# TeensySonarBoard.net
KiCad netlist of a schematic drawn in EAGLE
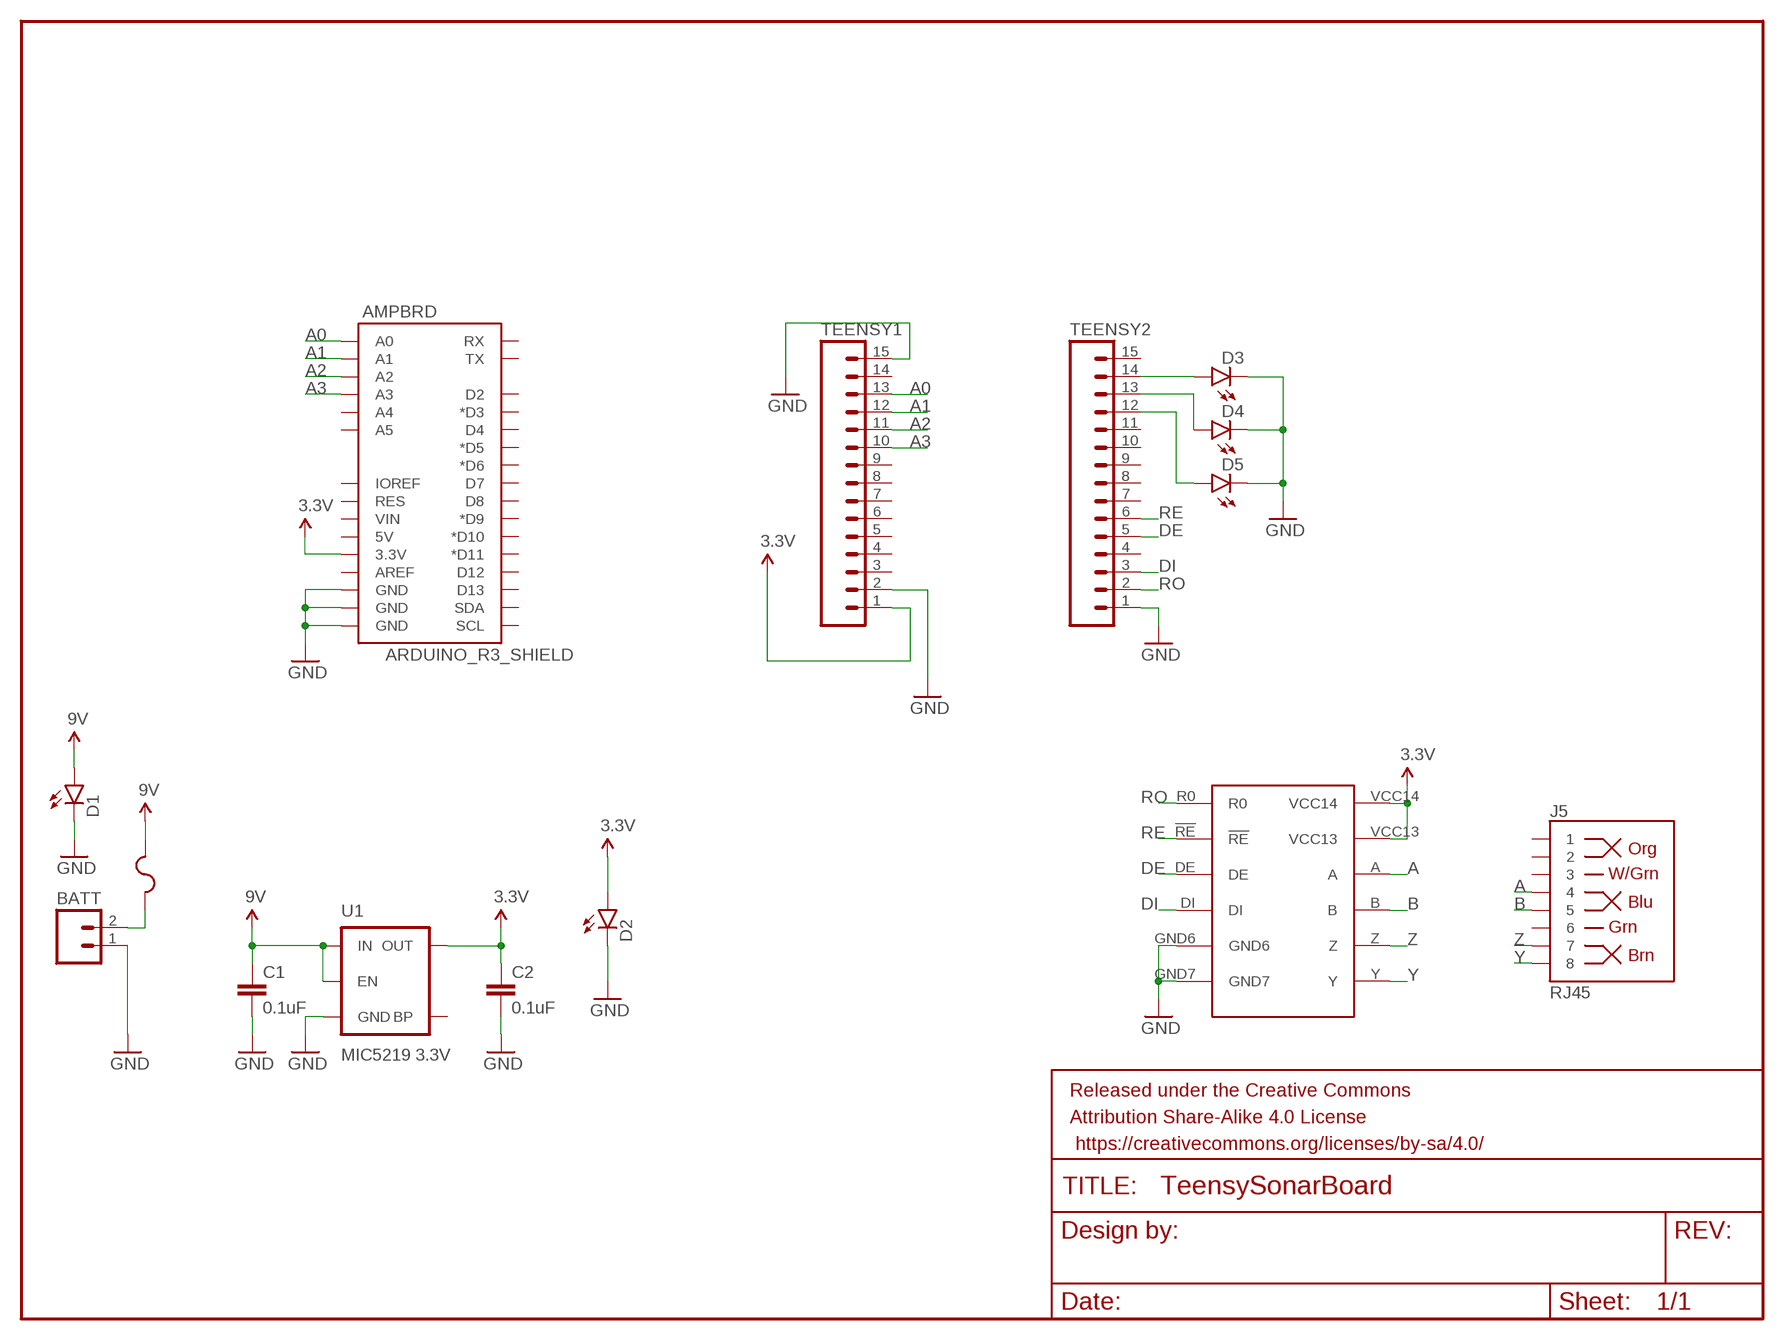
[diagram p0: schematic, sheet 1]

(export (version "E")
  (design (tool "Eeschema 10.0.6"))
  (components
    (comp (ref "AMPBRD")
      (value "ARDUINO_R3_SHIELD")
      (footprint "eagle-import:UNO_R3_SHIELD")
      (libsource (lib "eagle-import") (part "ARDUINO_R3_SHIELD"))
    )
    (comp (ref "BATT")
      (value "M02JST-PTH-VERT")
      (footprint "eagle-import:JST-2-PTH-VERT")
      (libsource (lib "eagle-import") (part "M02JST-PTH-VERT"))
    )
    (comp (ref "C1")
      (value "0.1uF")
      (footprint "eagle-import:0603-CAP")
      (libsource (lib "eagle-import") (part "CAP0603-CAP"))
    )
    (comp (ref "C2")
      (value "0.1uF")
      (footprint "eagle-import:0603-CAP")
      (libsource (lib "eagle-import") (part "CAP0603-CAP"))
    )
    (comp (ref "D1")
      (value "LED0603")
      (footprint "eagle-import:LED-0603")
      (libsource (lib "eagle-import") (part "LED0603"))
    )
    (comp (ref "D2")
      (value "LED0603")
      (footprint "eagle-import:LED-0603")
      (libsource (lib "eagle-import") (part "LED0603"))
    )
    (comp (ref "D3")
      (value "LED0603")
      (footprint "eagle-import:LED-0603")
      (libsource (lib "eagle-import") (part "LED0603"))
    )
    (comp (ref "D4")
      (value "LED0603")
      (footprint "eagle-import:LED-0603")
      (libsource (lib "eagle-import") (part "LED0603"))
    )
    (comp (ref "D5")
      (value "LED0603")
      (footprint "eagle-import:LED-0603")
      (libsource (lib "eagle-import") (part "LED0603"))
    )
    (comp (ref "F1")
      (value "2A")
      (footprint "eagle-import:KEYSTONE_FUSE_3587")
      (libsource (lib "eagle-import") (part "KEYSTONE_FUSE_3587"))
    )
    (comp (ref "FRAME1")
      (value "FRAME-LETTERNO_PACKAGE")
      (footprint "eagle-import:DUMMY")
      (fields (field (name "DESIGNER") "Nobody"))
      (libsource (lib "eagle-import") (part "FRAME-LETTERNO_PACKAGE"))
    )
    (comp (ref "J5")
      (value "RJ45")
      (footprint "eagle-import:RJ45-8")
      (libsource (lib "eagle-import") (part "RJ45-8PTH"))
    )
    (comp (ref "TEENSY1")
      (value "M15")
      (footprint "eagle-import:1X15")
      (libsource (lib "eagle-import") (part "M15"))
    )
    (comp (ref "TEENSY2")
      (value "M15")
      (footprint "eagle-import:1X15")
      (libsource (lib "eagle-import") (part "M15"))
    )
    (comp (ref "U$1")
      (value "MAX3491")
      (footprint "eagle-import:MAX3491")
      (libsource (lib "eagle-import") (part "MAX3491"))
    )
    (comp (ref "U1")
      (value "MIC5219 3.3V")
      (footprint "eagle-import:SOT23-5")
      (libsource (lib "eagle-import") (part "V_REG_MIC52193.3V"))
    )
  )
  (nets
    (net (code "1") (name "/A") (class "Default")
      (node (ref "J5") (pin "4") (pinfunction "4_4") (pintype "bidirectional"))
      (node (ref "U$1") (pin "A") (pinfunction "A_A") (pintype "bidirectional"))
    )
    (net (code "2") (name "/A0") (class "Default")
      (node (ref "AMPBRD") (pin "A0") (pinfunction "A0_A0") (pintype "bidirectional"))
      (node (ref "TEENSY1") (pin "13") (pinfunction "13_13") (pintype "passive"))
    )
    (net (code "3") (name "/A1") (class "Default")
      (node (ref "AMPBRD") (pin "A1") (pinfunction "A1_A1") (pintype "bidirectional"))
      (node (ref "TEENSY1") (pin "12") (pinfunction "12_12") (pintype "passive"))
    )
    (net (code "4") (name "/A2") (class "Default")
      (node (ref "AMPBRD") (pin "A2") (pinfunction "A2_A2") (pintype "bidirectional"))
      (node (ref "TEENSY1") (pin "11") (pinfunction "11_11") (pintype "passive"))
    )
    (net (code "5") (name "/A3") (class "Default")
      (node (ref "AMPBRD") (pin "A3") (pinfunction "A3_A3") (pintype "bidirectional"))
      (node (ref "TEENSY1") (pin "10") (pinfunction "10_10") (pintype "passive"))
    )
    (net (code "6") (name "/B") (class "Default")
      (node (ref "J5") (pin "5") (pinfunction "5_5") (pintype "bidirectional"))
      (node (ref "U$1") (pin "B") (pinfunction "B_B") (pintype "bidirectional"))
    )
    (net (code "7") (name "/DE") (class "Default")
      (node (ref "TEENSY2") (pin "5") (pinfunction "5_5") (pintype "passive"))
      (node (ref "U$1") (pin "DE") (pinfunction "DE_DE") (pintype "bidirectional"))
    )
    (net (code "8") (name "/DI") (class "Default")
      (node (ref "TEENSY2") (pin "3") (pinfunction "3_3") (pintype "passive"))
      (node (ref "U$1") (pin "DI") (pinfunction "DI_DI") (pintype "bidirectional"))
    )
    (net (code "9") (name "/RE") (class "Default")
      (node (ref "TEENSY2") (pin "6") (pinfunction "6_6") (pintype "passive"))
      (node (ref "U$1") (pin "!RE") (pinfunction "~{RE}_!RE") (pintype "bidirectional"))
    )
    (net (code "10") (name "/RO") (class "Default")
      (node (ref "TEENSY2") (pin "2") (pinfunction "2_2") (pintype "passive"))
      (node (ref "U$1") (pin "R0") (pinfunction "R0_R0") (pintype "bidirectional"))
    )
    (net (code "11") (name "/Y") (class "Default")
      (node (ref "J5") (pin "8") (pinfunction "8_8") (pintype "bidirectional"))
      (node (ref "U$1") (pin "Y") (pinfunction "Y_Y") (pintype "bidirectional"))
    )
    (net (code "12") (name "/Z") (class "Default")
      (node (ref "J5") (pin "7") (pinfunction "7_7") (pintype "bidirectional"))
      (node (ref "U$1") (pin "Z") (pinfunction "Z_Z") (pintype "bidirectional"))
    )
    (net (code "13") (name "3.3V") (class "Default")
      (node (ref "AMPBRD") (pin "3.3V") (pinfunction "3.3V_3.3V") (pintype "bidirectional"))
      (node (ref "C2") (pin "1") (pinfunction "1_1") (pintype "passive"))
      (node (ref "D2") (pin "A") (pinfunction "A_A") (pintype "passive"))
      (node (ref "TEENSY1") (pin "1") (pinfunction "1_1") (pintype "passive"))
      (node (ref "U$1") (pin "VCC13") (pinfunction "VCC13_VCC13") (pintype "bidirectional"))
      (node (ref "U$1") (pin "VCC14") (pinfunction "VCC14_VCC14") (pintype "bidirectional"))
      (node (ref "U1") (pin "5") (pinfunction "OUT_5") (pintype "passive"))
    )
    (net (code "14") (name "9V") (class "Default")
      (node (ref "C1") (pin "1") (pinfunction "1_1") (pintype "passive"))
      (node (ref "D1") (pin "A") (pinfunction "A_A") (pintype "passive"))
      (node (ref "F1") (pin "P$3") (pinfunction "P$2_P$3") (pintype "bidirectional"))
      (node (ref "F1") (pin "P$4") (pinfunction "P$2_P$4") (pintype "bidirectional"))
      (node (ref "U1") (pin "1") (pinfunction "IN_1") (pintype "input"))
      (node (ref "U1") (pin "3") (pinfunction "EN_3") (pintype "input"))
    )
    (net (code "15") (name "GND") (class "Default")
      (node (ref "AMPBRD") (pin "GND@0") (pinfunction "GND_GND@0") (pintype "bidirectional"))
      (node (ref "AMPBRD") (pin "GND@1") (pinfunction "GND_GND@1") (pintype "bidirectional"))
      (node (ref "AMPBRD") (pin "GND@2") (pinfunction "GND_GND@2") (pintype "bidirectional"))
      (node (ref "BATT") (pin "1") (pinfunction "1_1") (pintype "passive"))
      (node (ref "C1") (pin "2") (pinfunction "2_2") (pintype "passive"))
      (node (ref "C2") (pin "2") (pinfunction "2_2") (pintype "passive"))
      (node (ref "D1") (pin "C") (pinfunction "C_C") (pintype "passive"))
      (node (ref "D2") (pin "C") (pinfunction "C_C") (pintype "passive"))
      (node (ref "D3") (pin "C") (pinfunction "C_C") (pintype "passive"))
      (node (ref "D4") (pin "C") (pinfunction "C_C") (pintype "passive"))
      (node (ref "D5") (pin "C") (pinfunction "C_C") (pintype "passive"))
      (node (ref "TEENSY1") (pin "15") (pinfunction "15_15") (pintype "passive"))
      (node (ref "TEENSY1") (pin "2") (pinfunction "2_2") (pintype "passive"))
      (node (ref "TEENSY2") (pin "1") (pinfunction "1_1") (pintype "passive"))
      (node (ref "U$1") (pin "GND6") (pinfunction "GND6_GND6") (pintype "bidirectional"))
      (node (ref "U$1") (pin "GND7") (pinfunction "GND7_GND7") (pintype "bidirectional"))
      (node (ref "U1") (pin "2") (pinfunction "GND_2") (pintype "input"))
    )
    (net (code "16") (name "Net-(BATT-Pad2)") (class "Default")
      (node (ref "BATT") (pin "2") (pinfunction "2_2") (pintype "passive"))
      (node (ref "F1") (pin "P$1") (pinfunction "P$1_P$1") (pintype "bidirectional"))
      (node (ref "F1") (pin "P$2") (pinfunction "P$1_P$2") (pintype "bidirectional"))
    )
    (net (code "17") (name "Net-(D3-PadA)") (class "Default")
      (node (ref "D3") (pin "A") (pinfunction "A_A") (pintype "passive"))
      (node (ref "TEENSY2") (pin "14") (pinfunction "14_14") (pintype "passive"))
    )
    (net (code "18") (name "Net-(D4-PadA)") (class "Default")
      (node (ref "D4") (pin "A") (pinfunction "A_A") (pintype "passive"))
      (node (ref "TEENSY2") (pin "13") (pinfunction "13_13") (pintype "passive"))
    )
    (net (code "19") (name "Net-(D5-PadA)") (class "Default")
      (node (ref "D5") (pin "A") (pinfunction "A_A") (pintype "passive"))
      (node (ref "TEENSY2") (pin "12") (pinfunction "12_12") (pintype "passive"))
    )
    (net (code "20") (name "unconnected-(AMPBRD-*D3-PadD3)") (class "Default")
      (node (ref "AMPBRD") (pin "D3") (pinfunction "*D3_D3") (pintype "bidirectional"))
    )
    (net (code "21") (name "unconnected-(AMPBRD-*D5-PadD5)") (class "Default")
      (node (ref "AMPBRD") (pin "D5") (pinfunction "*D5_D5") (pintype "bidirectional"))
    )
    (net (code "22") (name "unconnected-(AMPBRD-*D6-PadD6)") (class "Default")
      (node (ref "AMPBRD") (pin "D6") (pinfunction "*D6_D6") (pintype "bidirectional"))
    )
    (net (code "23") (name "unconnected-(AMPBRD-*D9-PadD9)") (class "Default")
      (node (ref "AMPBRD") (pin "D9") (pinfunction "*D9_D9") (pintype "bidirectional"))
    )
    (net (code "24") (name "unconnected-(AMPBRD-*D10-PadD10)") (class "Default")
      (node (ref "AMPBRD") (pin "D10") (pinfunction "*D10_D10") (pintype "bidirectional"))
    )
    (net (code "25") (name "unconnected-(AMPBRD-*D11-PadD11)") (class "Default")
      (node (ref "AMPBRD") (pin "D11") (pinfunction "*D11_D11") (pintype "bidirectional"))
    )
    (net (code "26") (name "unconnected-(AMPBRD-Pad5V)") (class "Default")
      (node (ref "AMPBRD") (pin "5V") (pinfunction "5V_5V") (pintype "bidirectional"))
    )
    (net (code "27") (name "unconnected-(AMPBRD-PadA4)") (class "Default")
      (node (ref "AMPBRD") (pin "A4") (pinfunction "A4_A4") (pintype "bidirectional"))
    )
    (net (code "28") (name "unconnected-(AMPBRD-PadA5)") (class "Default")
      (node (ref "AMPBRD") (pin "A5") (pinfunction "A5_A5") (pintype "bidirectional"))
    )
    (net (code "29") (name "unconnected-(AMPBRD-PadAREF)") (class "Default")
      (node (ref "AMPBRD") (pin "AREF") (pinfunction "AREF_AREF") (pintype "bidirectional"))
    )
    (net (code "30") (name "unconnected-(AMPBRD-PadD2)") (class "Default")
      (node (ref "AMPBRD") (pin "D2") (pinfunction "D2_D2") (pintype "bidirectional"))
    )
    (net (code "31") (name "unconnected-(AMPBRD-PadD4)") (class "Default")
      (node (ref "AMPBRD") (pin "D4") (pinfunction "D4_D4") (pintype "bidirectional"))
    )
    (net (code "32") (name "unconnected-(AMPBRD-PadD7)") (class "Default")
      (node (ref "AMPBRD") (pin "D7") (pinfunction "D7_D7") (pintype "bidirectional"))
    )
    (net (code "33") (name "unconnected-(AMPBRD-PadD8)") (class "Default")
      (node (ref "AMPBRD") (pin "D8") (pinfunction "D8_D8") (pintype "bidirectional"))
    )
    (net (code "34") (name "unconnected-(AMPBRD-PadD12)") (class "Default")
      (node (ref "AMPBRD") (pin "D12") (pinfunction "D12_D12") (pintype "bidirectional"))
    )
    (net (code "35") (name "unconnected-(AMPBRD-PadD13)") (class "Default")
      (node (ref "AMPBRD") (pin "D13") (pinfunction "D13_D13") (pintype "bidirectional"))
    )
    (net (code "36") (name "unconnected-(AMPBRD-PadIOREF)") (class "Default")
      (node (ref "AMPBRD") (pin "IOREF") (pinfunction "IOREF_IOREF") (pintype "bidirectional"))
    )
    (net (code "37") (name "unconnected-(AMPBRD-PadRES)") (class "Default")
      (node (ref "AMPBRD") (pin "RES") (pinfunction "RES_RES") (pintype "bidirectional"))
    )
    (net (code "38") (name "unconnected-(AMPBRD-PadRX)") (class "Default")
      (node (ref "AMPBRD") (pin "RX") (pinfunction "RX_RX") (pintype "bidirectional"))
    )
    (net (code "39") (name "unconnected-(AMPBRD-PadSCL)") (class "Default")
      (node (ref "AMPBRD") (pin "SCL") (pinfunction "SCL_SCL") (pintype "bidirectional"))
    )
    (net (code "40") (name "unconnected-(AMPBRD-PadSDA)") (class "Default")
      (node (ref "AMPBRD") (pin "SDA") (pinfunction "SDA_SDA") (pintype "bidirectional"))
    )
    (net (code "41") (name "unconnected-(AMPBRD-PadTX)") (class "Default")
      (node (ref "AMPBRD") (pin "TX") (pinfunction "TX_TX") (pintype "bidirectional"))
    )
    (net (code "42") (name "unconnected-(AMPBRD-PadVIN)") (class "Default")
      (node (ref "AMPBRD") (pin "VIN") (pinfunction "VIN_VIN") (pintype "bidirectional"))
    )
    (net (code "43") (name "unconnected-(J5-Pad1)") (class "Default")
      (node (ref "J5") (pin "1") (pinfunction "1_1") (pintype "bidirectional"))
    )
    (net (code "44") (name "unconnected-(J5-Pad2)") (class "Default")
      (node (ref "J5") (pin "2") (pinfunction "2_2") (pintype "bidirectional"))
    )
    (net (code "45") (name "unconnected-(J5-Pad3)") (class "Default")
      (node (ref "J5") (pin "3") (pinfunction "3_3") (pintype "bidirectional"))
    )
    (net (code "46") (name "unconnected-(J5-Pad6)") (class "Default")
      (node (ref "J5") (pin "6") (pinfunction "6_6") (pintype "bidirectional"))
    )
    (net (code "47") (name "unconnected-(TEENSY1-Pad3)") (class "Default")
      (node (ref "TEENSY1") (pin "3") (pinfunction "3_3") (pintype "passive"))
    )
    (net (code "48") (name "unconnected-(TEENSY1-Pad4)") (class "Default")
      (node (ref "TEENSY1") (pin "4") (pinfunction "4_4") (pintype "passive"))
    )
    (net (code "49") (name "unconnected-(TEENSY1-Pad5)") (class "Default")
      (node (ref "TEENSY1") (pin "5") (pinfunction "5_5") (pintype "passive"))
    )
    (net (code "50") (name "unconnected-(TEENSY1-Pad6)") (class "Default")
      (node (ref "TEENSY1") (pin "6") (pinfunction "6_6") (pintype "passive"))
    )
    (net (code "51") (name "unconnected-(TEENSY1-Pad7)") (class "Default")
      (node (ref "TEENSY1") (pin "7") (pinfunction "7_7") (pintype "passive"))
    )
    (net (code "52") (name "unconnected-(TEENSY1-Pad8)") (class "Default")
      (node (ref "TEENSY1") (pin "8") (pinfunction "8_8") (pintype "passive"))
    )
    (net (code "53") (name "unconnected-(TEENSY1-Pad9)") (class "Default")
      (node (ref "TEENSY1") (pin "9") (pinfunction "9_9") (pintype "passive"))
    )
    (net (code "54") (name "unconnected-(TEENSY1-Pad14)") (class "Default")
      (node (ref "TEENSY1") (pin "14") (pinfunction "14_14") (pintype "passive"))
    )
    (net (code "55") (name "unconnected-(TEENSY2-Pad4)") (class "Default")
      (node (ref "TEENSY2") (pin "4") (pinfunction "4_4") (pintype "passive"))
    )
    (net (code "56") (name "unconnected-(TEENSY2-Pad7)") (class "Default")
      (node (ref "TEENSY2") (pin "7") (pinfunction "7_7") (pintype "passive"))
    )
    (net (code "57") (name "unconnected-(TEENSY2-Pad8)") (class "Default")
      (node (ref "TEENSY2") (pin "8") (pinfunction "8_8") (pintype "passive"))
    )
    (net (code "58") (name "unconnected-(TEENSY2-Pad9)") (class "Default")
      (node (ref "TEENSY2") (pin "9") (pinfunction "9_9") (pintype "passive"))
    )
    (net (code "59") (name "unconnected-(TEENSY2-Pad10)") (class "Default")
      (node (ref "TEENSY2") (pin "10") (pinfunction "10_10") (pintype "passive"))
    )
    (net (code "60") (name "unconnected-(TEENSY2-Pad11)") (class "Default")
      (node (ref "TEENSY2") (pin "11") (pinfunction "11_11") (pintype "passive"))
    )
    (net (code "61") (name "unconnected-(TEENSY2-Pad15)") (class "Default")
      (node (ref "TEENSY2") (pin "15") (pinfunction "15_15") (pintype "passive"))
    )
    (net (code "62") (name "unconnected-(U1-BP-Pad4)") (class "Default")
      (node (ref "U1") (pin "4") (pinfunction "BP_4") (pintype "input"))
    )
  )
)
